# 4_board.net
KiCad netlist of a schematic drawn in EAGLE
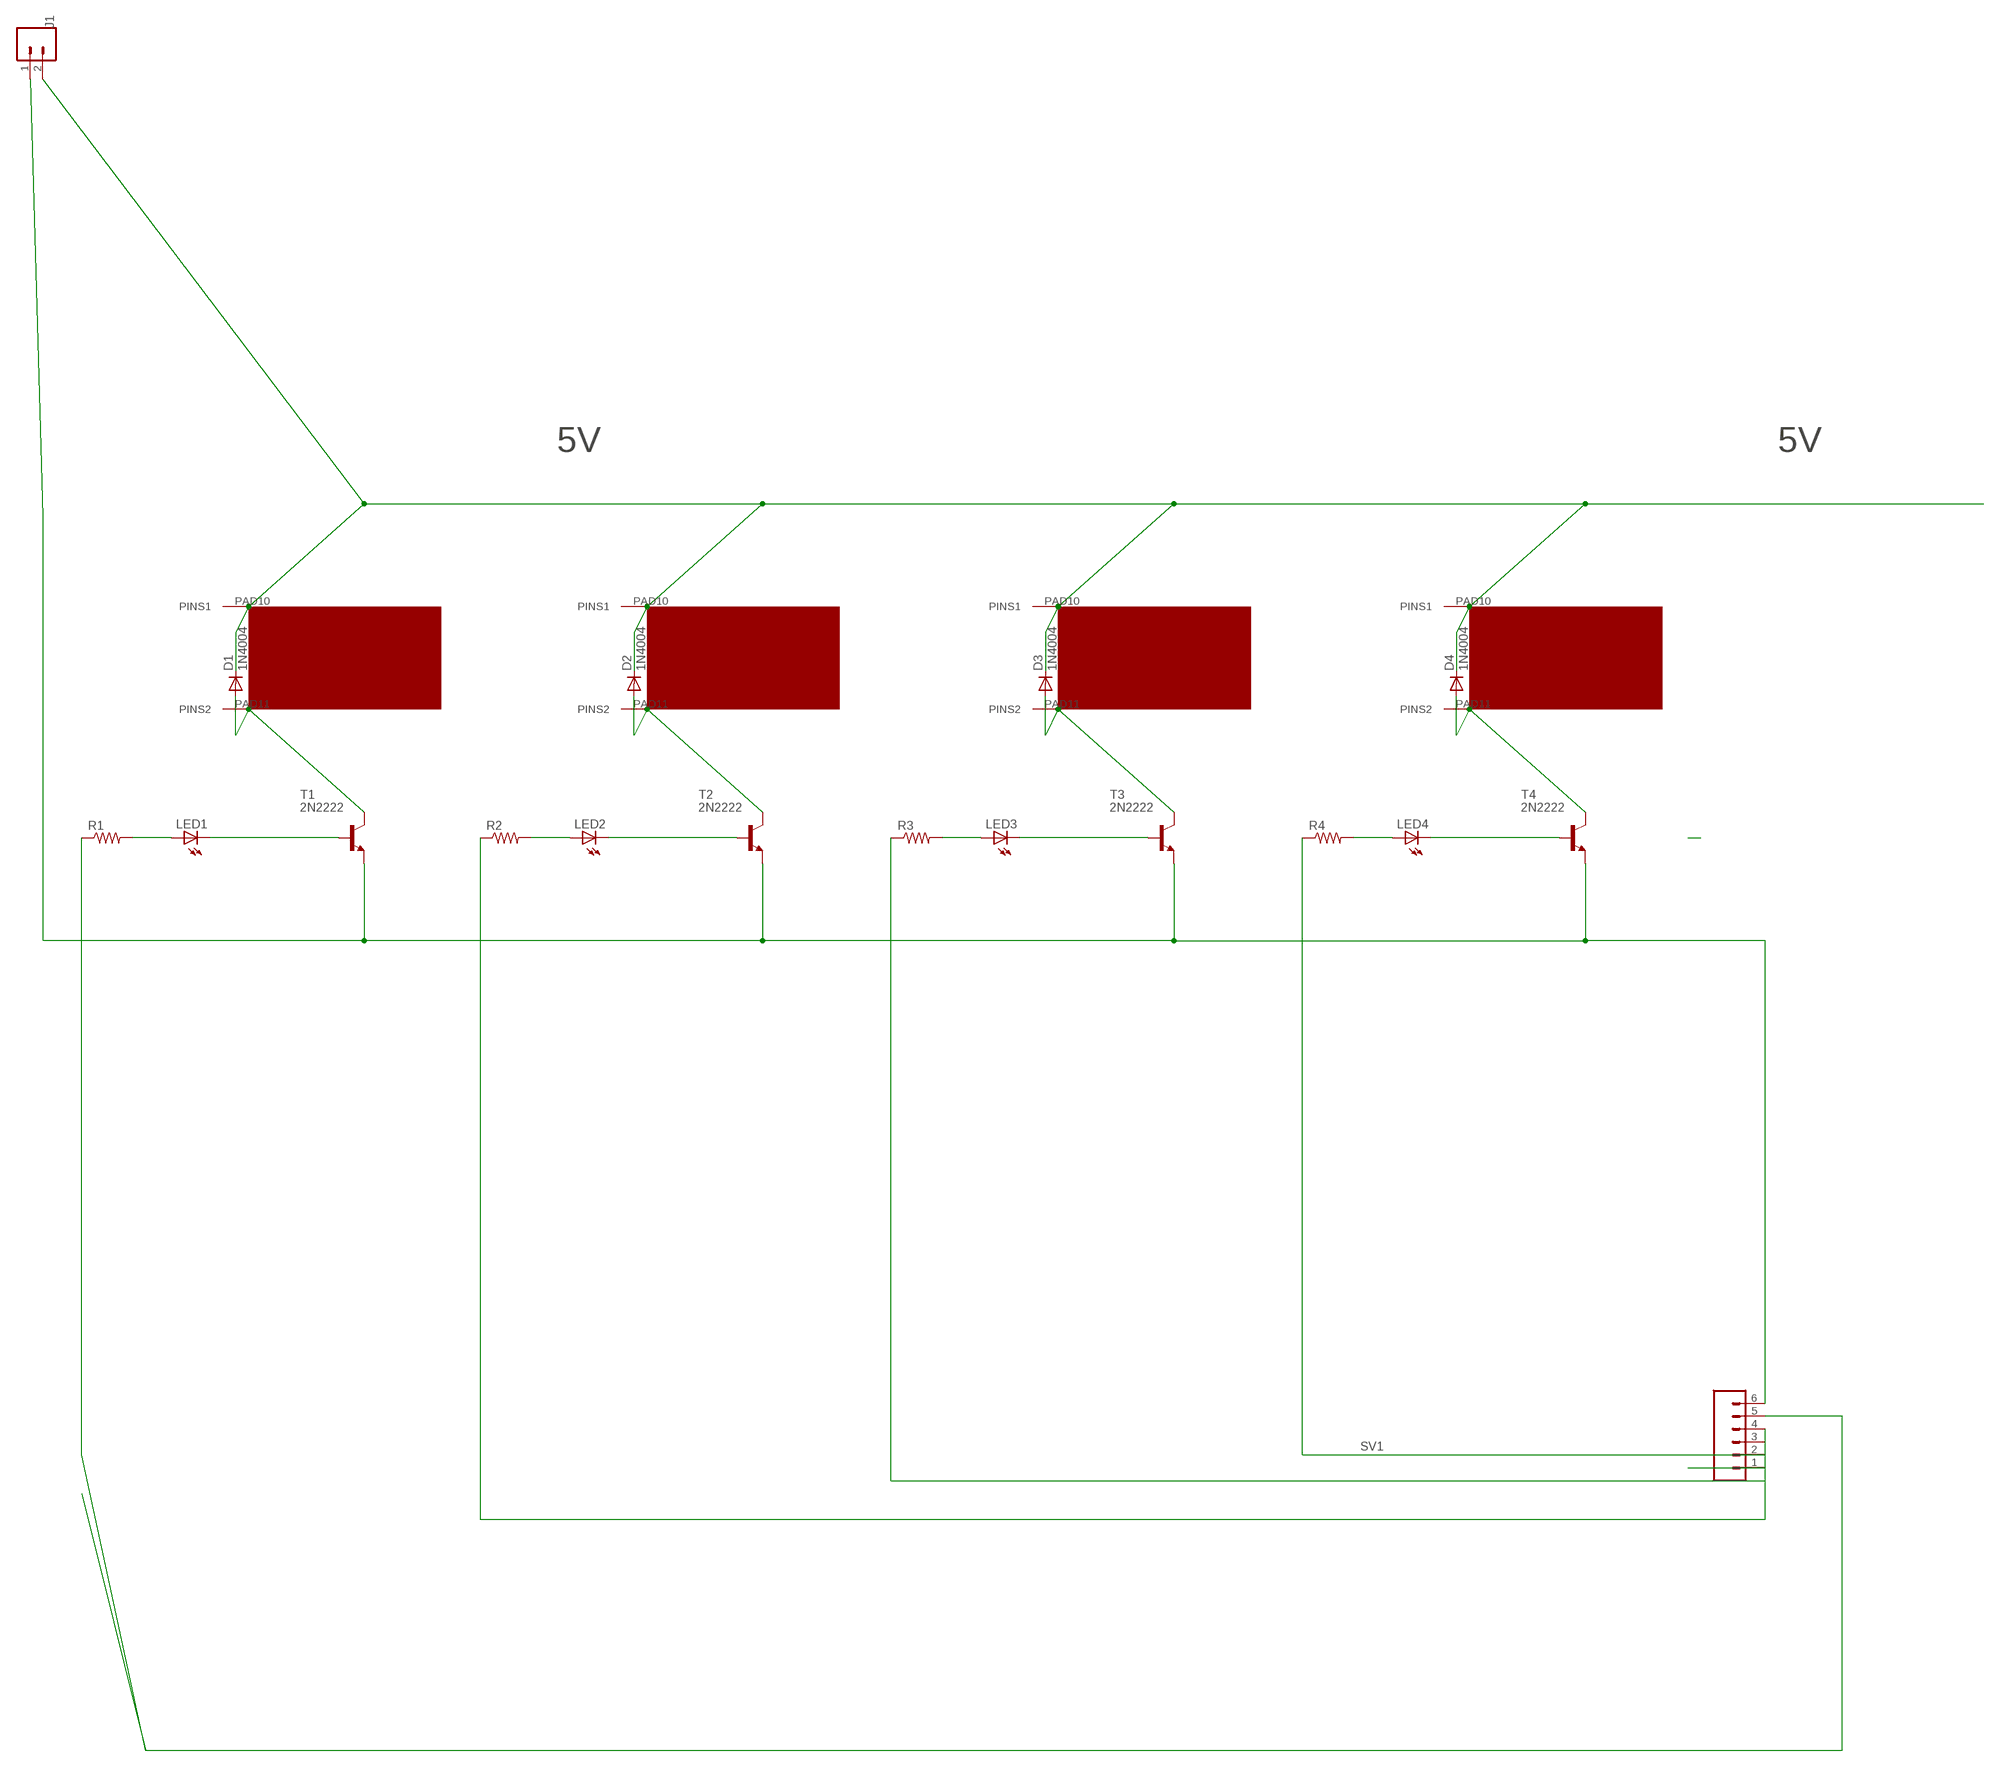
[diagram p0: schematic, sheet 1]

(export (version "E")
  (design (tool "Eeschema 10.0.6"))
  (components
    (comp (ref "D1")
      (value "1N4004")
      (footprint "eagle-import:DO41-10")
      (libsource (lib "eagle-import") (part "1N4004"))
    )
    (comp (ref "D2")
      (value "1N4004")
      (footprint "eagle-import:DO41-10")
      (libsource (lib "eagle-import") (part "1N4004"))
    )
    (comp (ref "D3")
      (value "1N4004")
      (footprint "eagle-import:DO41-10")
      (libsource (lib "eagle-import") (part "1N4004"))
    )
    (comp (ref "D4")
      (value "1N4004")
      (footprint "eagle-import:DO41-10")
      (libsource (lib "eagle-import") (part "1N4004"))
    )
    (comp (ref "J1")
      (value "CONN_023.5MM")
      (footprint "eagle-import:SCREWTERMINAL-3.5MM-2")
      (libsource (lib "eagle-import") (part "CONN_023.5MM"))
    )
    (comp (ref "LED1")
      (value "LED5MM")
      (footprint "eagle-import:LED5MM")
      (libsource (lib "eagle-import") (part "LED5MM"))
    )
    (comp (ref "LED2")
      (value "LED5MM")
      (footprint "eagle-import:LED5MM")
      (libsource (lib "eagle-import") (part "LED5MM"))
    )
    (comp (ref "LED3")
      (value "LED5MM")
      (footprint "eagle-import:LED5MM")
      (libsource (lib "eagle-import") (part "LED5MM"))
    )
    (comp (ref "LED4")
      (value "LED5MM")
      (footprint "eagle-import:LED5MM")
      (libsource (lib "eagle-import") (part "LED5MM"))
    )
    (comp (ref "R1")
      (value "R-US_0207/10")
      (footprint "eagle-import:0207_10")
      (libsource (lib "eagle-import") (part "R-US_0207/10"))
    )
    (comp (ref "R2")
      (value "R-US_0207/10")
      (footprint "eagle-import:0207_10")
      (libsource (lib "eagle-import") (part "R-US_0207/10"))
    )
    (comp (ref "R3")
      (value "R-US_0207/10")
      (footprint "eagle-import:0207_10")
      (libsource (lib "eagle-import") (part "R-US_0207/10"))
    )
    (comp (ref "R4")
      (value "R-US_0207/10")
      (footprint "eagle-import:0207_10")
      (libsource (lib "eagle-import") (part "R-US_0207/10"))
    )
    (comp (ref "SV1")
      (value "CONN_06LOCK")
      (footprint "eagle-import:1X06_LOCK")
      (libsource (lib "eagle-import") (part "CONN_06LOCK"))
    )
    (comp (ref "T1")
      (value "2N2222")
      (footprint "eagle-import:TO92-EBC-OVAL")
      (libsource (lib "eagle-import") (part "2N2222"))
    )
    (comp (ref "T2")
      (value "2N2222")
      (footprint "eagle-import:TO92-EBC-OVAL")
      (libsource (lib "eagle-import") (part "2N2222"))
    )
    (comp (ref "T3")
      (value "2N2222")
      (footprint "eagle-import:TO92-EBC-OVAL")
      (libsource (lib "eagle-import") (part "2N2222"))
    )
    (comp (ref "T4")
      (value "2N2222")
      (footprint "eagle-import:TO92-EBC-OVAL")
      (libsource (lib "eagle-import") (part "2N2222"))
    )
    (comp (ref "U$1")
      (value "VALVE")
      (footprint "eagle-import:VALVTEST2")
      (libsource (lib "eagle-import") (part "VALVE"))
    )
    (comp (ref "U$2")
      (value "VALVE")
      (footprint "eagle-import:VALVTEST2")
      (libsource (lib "eagle-import") (part "VALVE"))
    )
    (comp (ref "VALVE3")
      (value "VALVE")
      (footprint "eagle-import:VALVTEST2")
      (libsource (lib "eagle-import") (part "VALVE"))
    )
    (comp (ref "VALVE4")
      (value "4")
      (footprint "eagle-import:VALVTEST2")
      (libsource (lib "eagle-import") (part "VALVE"))
    )
  )
  (nets
    (net (code "1") (name "/5V") (class "Default")
      (node (ref "D1") (pin "C") (pinfunction "C_C") (pintype "passive"))
      (node (ref "D2") (pin "C") (pinfunction "C_C") (pintype "passive"))
      (node (ref "D3") (pin "C") (pinfunction "C_C") (pintype "passive"))
      (node (ref "D4") (pin "C") (pinfunction "C_C") (pintype "passive"))
      (node (ref "J1") (pin "2") (pinfunction "2_2") (pintype "passive"))
      (node (ref "U$1") (pin "PAD10") (pinfunction "PINS1_PAD10") (pintype "bidirectional"))
      (node (ref "U$2") (pin "PAD10") (pinfunction "PINS1_PAD10") (pintype "bidirectional"))
      (node (ref "VALVE3") (pin "PAD10") (pinfunction "PINS1_PAD10") (pintype "bidirectional"))
      (node (ref "VALVE4") (pin "PAD10") (pinfunction "PINS1_PAD10") (pintype "bidirectional"))
    )
    (net (code "2") (name "Net-(J1-Pad1)") (class "Default")
      (node (ref "J1") (pin "1") (pinfunction "1_1") (pintype "passive"))
      (node (ref "SV1") (pin "6") (pinfunction "6_6") (pintype "passive"))
      (node (ref "T1") (pin "E") (pinfunction "E_E") (pintype "passive"))
      (node (ref "T2") (pin "E") (pinfunction "E_E") (pintype "passive"))
      (node (ref "T3") (pin "E") (pinfunction "E_E") (pintype "passive"))
      (node (ref "T4") (pin "E") (pinfunction "E_E") (pintype "passive"))
    )
    (net (code "3") (name "Net-(LED1-C)") (class "Default")
      (node (ref "LED1") (pin "K") (pinfunction "C_K") (pintype "passive"))
      (node (ref "T1") (pin "B") (pinfunction "B_B") (pintype "passive"))
    )
    (net (code "4") (name "Net-(LED1-PadA)") (class "Default")
      (node (ref "LED1") (pin "A") (pinfunction "A_A") (pintype "passive"))
      (node (ref "R1") (pin "2") (pinfunction "2_2") (pintype "passive"))
    )
    (net (code "5") (name "Net-(LED2-C)") (class "Default")
      (node (ref "LED2") (pin "K") (pinfunction "C_K") (pintype "passive"))
      (node (ref "T2") (pin "B") (pinfunction "B_B") (pintype "passive"))
    )
    (net (code "6") (name "Net-(LED2-PadA)") (class "Default")
      (node (ref "LED2") (pin "A") (pinfunction "A_A") (pintype "passive"))
      (node (ref "R2") (pin "2") (pinfunction "2_2") (pintype "passive"))
    )
    (net (code "7") (name "Net-(LED3-C)") (class "Default")
      (node (ref "LED3") (pin "K") (pinfunction "C_K") (pintype "passive"))
      (node (ref "T3") (pin "B") (pinfunction "B_B") (pintype "passive"))
    )
    (net (code "8") (name "Net-(LED3-PadA)") (class "Default")
      (node (ref "LED3") (pin "A") (pinfunction "A_A") (pintype "passive"))
      (node (ref "R3") (pin "2") (pinfunction "2_2") (pintype "passive"))
    )
    (net (code "9") (name "Net-(LED4-C)") (class "Default")
      (node (ref "LED4") (pin "K") (pinfunction "C_K") (pintype "passive"))
      (node (ref "T4") (pin "B") (pinfunction "B_B") (pintype "passive"))
    )
    (net (code "10") (name "Net-(LED4-PadA)") (class "Default")
      (node (ref "LED4") (pin "A") (pinfunction "A_A") (pintype "passive"))
      (node (ref "R4") (pin "2") (pinfunction "2_2") (pintype "passive"))
    )
    (net (code "11") (name "Net-(R1-Pad1)") (class "Default")
      (node (ref "R1") (pin "1") (pinfunction "1_1") (pintype "passive"))
      (node (ref "SV1") (pin "5") (pinfunction "5_5") (pintype "passive"))
    )
    (net (code "12") (name "Net-(R2-Pad1)") (class "Default")
      (node (ref "R2") (pin "1") (pinfunction "1_1") (pintype "passive"))
      (node (ref "SV1") (pin "4") (pinfunction "4_4") (pintype "passive"))
    )
    (net (code "13") (name "Net-(R3-Pad1)") (class "Default")
      (node (ref "R3") (pin "1") (pinfunction "1_1") (pintype "passive"))
      (node (ref "SV1") (pin "3") (pinfunction "3_3") (pintype "passive"))
    )
    (net (code "14") (name "Net-(R4-Pad1)") (class "Default")
      (node (ref "R4") (pin "1") (pinfunction "1_1") (pintype "passive"))
      (node (ref "SV1") (pin "2") (pinfunction "2_2") (pintype "passive"))
    )
    (net (code "15") (name "Net-(U$1-PINS2)") (class "Default")
      (node (ref "D1") (pin "A") (pinfunction "A_A") (pintype "passive"))
      (node (ref "T1") (pin "C") (pinfunction "C_C") (pintype "passive"))
      (node (ref "U$1") (pin "PAD11") (pinfunction "PINS2_PAD11") (pintype "bidirectional"))
    )
    (net (code "16") (name "Net-(U$2-PINS2)") (class "Default")
      (node (ref "D2") (pin "A") (pinfunction "A_A") (pintype "passive"))
      (node (ref "T2") (pin "C") (pinfunction "C_C") (pintype "passive"))
      (node (ref "U$2") (pin "PAD11") (pinfunction "PINS2_PAD11") (pintype "bidirectional"))
    )
    (net (code "17") (name "Net-(VALVE3-PINS2)") (class "Default")
      (node (ref "D3") (pin "A") (pinfunction "A_A") (pintype "passive"))
      (node (ref "T3") (pin "C") (pinfunction "C_C") (pintype "passive"))
      (node (ref "VALVE3") (pin "PAD11") (pinfunction "PINS2_PAD11") (pintype "bidirectional"))
    )
    (net (code "18") (name "Net-(VALVE4-PINS2)") (class "Default")
      (node (ref "D4") (pin "A") (pinfunction "A_A") (pintype "passive"))
      (node (ref "T4") (pin "C") (pinfunction "C_C") (pintype "passive"))
      (node (ref "VALVE4") (pin "PAD11") (pinfunction "PINS2_PAD11") (pintype "bidirectional"))
    )
    (net (code "19") (name "unconnected-(SV1-Pad1)") (class "Default")
      (node (ref "SV1") (pin "1") (pinfunction "1_1") (pintype "passive"))
    )
  )
)
